# Pneumatics.net
KiCad netlist of a schematic drawn in Altium Designer
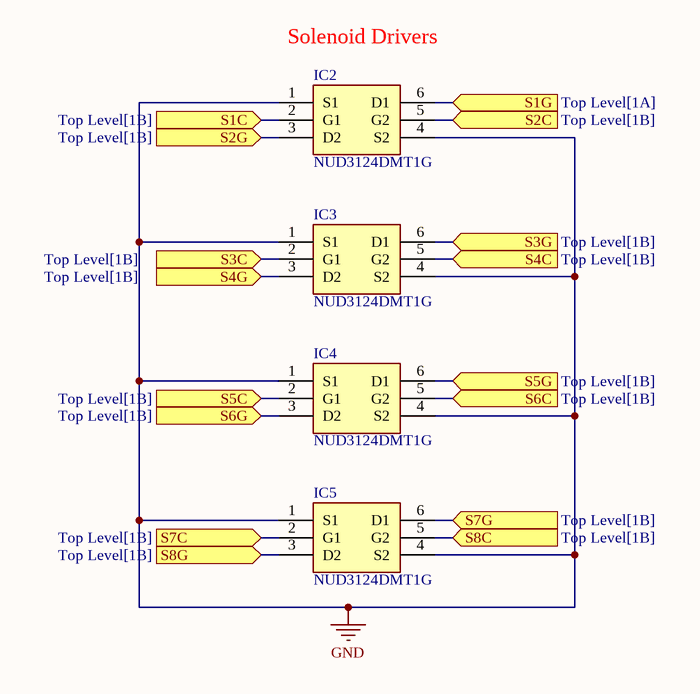
[diagram p0: Pneumatics.SchDoc]

(export (version "E")
  (design (tool "Eeschema 10.0.6"))
  (components
    (comp (ref "IC2")
      (value "NUD3124DMT1G")
      (footprint "SOT95P275X110-6N")
      (description "Integrated Circuit")
      (fields (field (name "MOUSER PART NUMBER") "863-NUD3124DMT1G"))
      (libsource (lib "SamacSys") (part "NUD3124DMT1G"))
    )
    (comp (ref "IC3")
      (value "NUD3124DMT1G")
      (footprint "SOT95P275X110-6N")
      (description "Integrated Circuit")
      (fields (field (name "MOUSER PART NUMBER") "863-NUD3124DMT1G"))
      (libsource (lib "SamacSys") (part "NUD3124DMT1G"))
    )
    (comp (ref "IC4")
      (value "NUD3124DMT1G")
      (footprint "SOT95P275X110-6N")
      (description "Integrated Circuit")
      (fields (field (name "MOUSER PART NUMBER") "863-NUD3124DMT1G"))
      (libsource (lib "SamacSys") (part "NUD3124DMT1G"))
    )
    (comp (ref "IC5")
      (value "NUD3124DMT1G")
      (footprint "SOT95P275X110-6N")
      (description "Integrated Circuit")
      (fields (field (name "MOUSER PART NUMBER") "863-NUD3124DMT1G"))
      (libsource (lib "SamacSys") (part "NUD3124DMT1G"))
    )
  )
  (nets
    (net (code "1") (name "/S1C") (class "Default")
      (node (ref "IC2") (pin "2") (pinfunction "G1_2") (pintype "passive"))
    )
    (net (code "2") (name "/S1G") (class "Default")
      (node (ref "IC2") (pin "6") (pinfunction "D1_6") (pintype "passive"))
    )
    (net (code "3") (name "/S2C") (class "Default")
      (node (ref "IC2") (pin "5") (pinfunction "G2_5") (pintype "passive"))
    )
    (net (code "4") (name "/S2G") (class "Default")
      (node (ref "IC2") (pin "3") (pinfunction "D2_3") (pintype "passive"))
    )
    (net (code "5") (name "/S3C") (class "Default")
      (node (ref "IC3") (pin "2") (pinfunction "G1_2") (pintype "passive"))
    )
    (net (code "6") (name "/S3G") (class "Default")
      (node (ref "IC3") (pin "6") (pinfunction "D1_6") (pintype "passive"))
    )
    (net (code "7") (name "/S4C") (class "Default")
      (node (ref "IC3") (pin "5") (pinfunction "G2_5") (pintype "passive"))
    )
    (net (code "8") (name "/S4G") (class "Default")
      (node (ref "IC3") (pin "3") (pinfunction "D2_3") (pintype "passive"))
    )
    (net (code "9") (name "/S5C") (class "Default")
      (node (ref "IC4") (pin "2") (pinfunction "G1_2") (pintype "passive"))
    )
    (net (code "10") (name "/S5G") (class "Default")
      (node (ref "IC4") (pin "6") (pinfunction "D1_6") (pintype "passive"))
    )
    (net (code "11") (name "/S6C") (class "Default")
      (node (ref "IC4") (pin "5") (pinfunction "G2_5") (pintype "passive"))
    )
    (net (code "12") (name "/S6G") (class "Default")
      (node (ref "IC4") (pin "3") (pinfunction "D2_3") (pintype "passive"))
    )
    (net (code "13") (name "/S7C") (class "Default")
      (node (ref "IC5") (pin "2") (pinfunction "G1_2") (pintype "passive"))
    )
    (net (code "14") (name "/S7G") (class "Default")
      (node (ref "IC5") (pin "6") (pinfunction "D1_6") (pintype "passive"))
    )
    (net (code "15") (name "/S8C") (class "Default")
      (node (ref "IC5") (pin "5") (pinfunction "G2_5") (pintype "passive"))
    )
    (net (code "16") (name "/S8G") (class "Default")
      (node (ref "IC5") (pin "3") (pinfunction "D2_3") (pintype "passive"))
    )
    (net (code "17") (name "GND") (class "Default")
      (node (ref "IC2") (pin "1") (pinfunction "S1_1") (pintype "passive"))
      (node (ref "IC2") (pin "4") (pinfunction "S2_4") (pintype "passive"))
      (node (ref "IC3") (pin "1") (pinfunction "S1_1") (pintype "passive"))
      (node (ref "IC3") (pin "4") (pinfunction "S2_4") (pintype "passive"))
      (node (ref "IC4") (pin "1") (pinfunction "S1_1") (pintype "passive"))
      (node (ref "IC4") (pin "4") (pinfunction "S2_4") (pintype "passive"))
      (node (ref "IC5") (pin "1") (pinfunction "S1_1") (pintype "passive"))
      (node (ref "IC5") (pin "4") (pinfunction "S2_4") (pintype "passive"))
    )
  )
)
